# rapidshark-half-h-bridge-mk-1_0.net
KiCad netlist of a schematic drawn in EAGLE
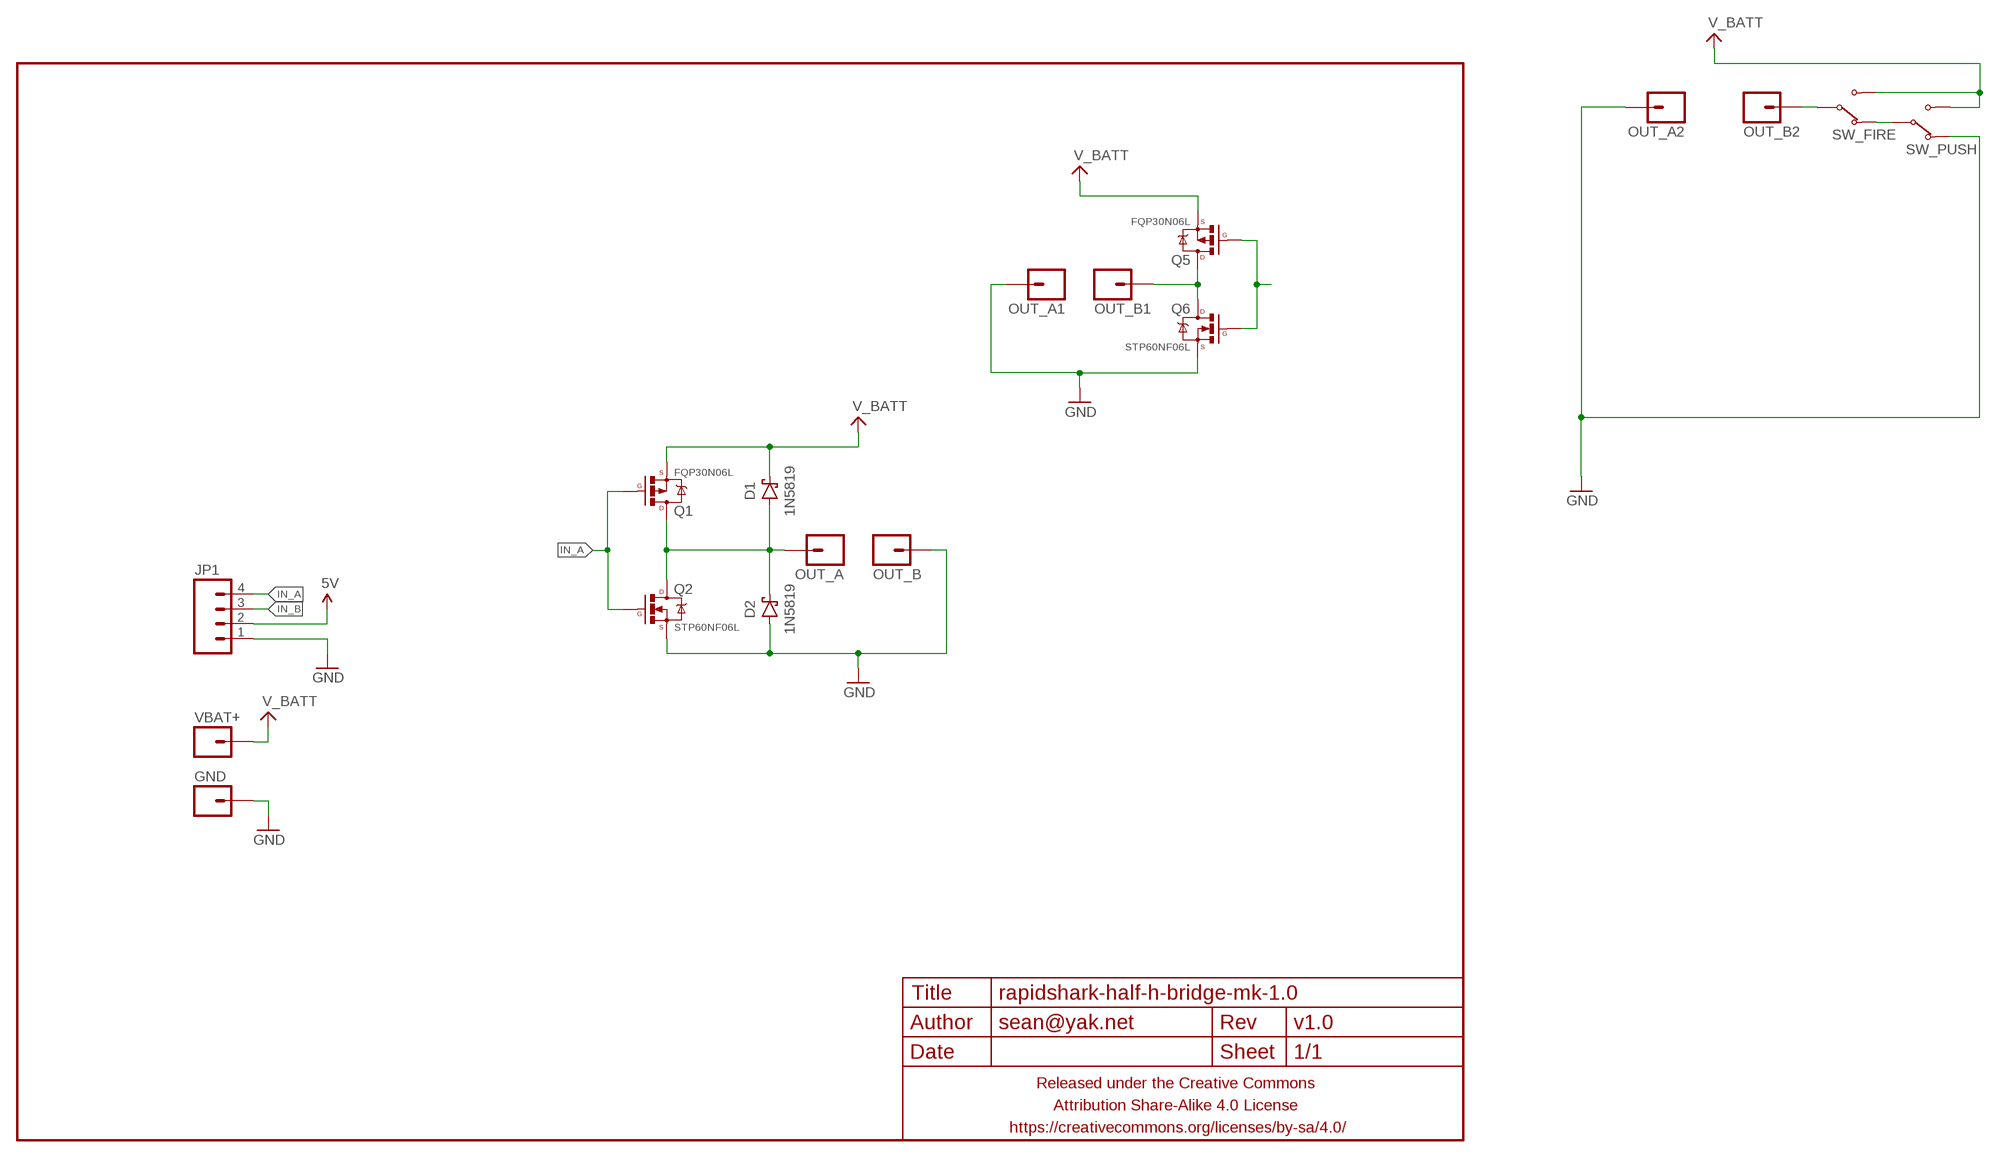
[diagram p0: schematic, sheet 1]

(export (version "E")
  (design (tool "Eeschema 10.0.6"))
  (components
    (comp (ref "D1")
      (value "1N5819")
      (footprint "eagle-import:DIODE-SCHOTTKY-10.16MM")
      (libsource (lib "eagle-import") (part "DIODE-SCHOTTKYPTH-10.16MM"))
    )
    (comp (ref "D2")
      (value "1N5819")
      (footprint "eagle-import:DIODE-SCHOTTKY-10.16MM")
      (libsource (lib "eagle-import") (part "DIODE-SCHOTTKYPTH-10.16MM"))
    )
    (comp (ref "FRAME1")
      (value "FRAME-LETTERNO_PACKAGE")
      (footprint "eagle-import:DUMMY")
      (fields (field (name "DESIGNER") "sean@yak.net") (field (name "VERSION") "v1.0"))
      (libsource (lib "eagle-import") (part "FRAME-LETTERNO_PACKAGE"))
    )
    (comp (ref "GND")
      (value "M0112AWG")
      (footprint "eagle-import:1X01-12AWG")
      (libsource (lib "eagle-import") (part "M0112AWG"))
    )
    (comp (ref "JP1")
      (value "M04PTH")
      (footprint "eagle-import:1X04-PTH-VERT")
      (libsource (lib "eagle-import") (part "M04PTH"))
    )
    (comp (ref "OUT_A")
      (value "M0112AWG")
      (footprint "eagle-import:1X01-12AWG")
      (libsource (lib "eagle-import") (part "M0112AWG"))
    )
    (comp (ref "OUT_A1")
      (value "M0112AWG")
      (footprint "eagle-import:1X01-12AWG")
      (libsource (lib "eagle-import") (part "M0112AWG"))
    )
    (comp (ref "OUT_A2")
      (value "M0112AWG")
      (footprint "eagle-import:1X01-12AWG")
      (libsource (lib "eagle-import") (part "M0112AWG"))
    )
    (comp (ref "OUT_B")
      (value "M0112AWG")
      (footprint "eagle-import:1X01-12AWG")
      (libsource (lib "eagle-import") (part "M0112AWG"))
    )
    (comp (ref "OUT_B1")
      (value "M0112AWG")
      (footprint "eagle-import:1X01-12AWG")
      (libsource (lib "eagle-import") (part "M0112AWG"))
    )
    (comp (ref "OUT_B2")
      (value "M0112AWG")
      (footprint "eagle-import:1X01-12AWG")
      (libsource (lib "eagle-import") (part "M0112AWG"))
    )
    (comp (ref "Q1")
      (value "FQP30N06L")
      (footprint "eagle-import:TO220-THERMPAD")
      (libsource (lib "eagle-import") (part "MOSFET-PCHANNELTO-220-THERMPAD"))
    )
    (comp (ref "Q2")
      (value "STP60NF06L")
      (footprint "eagle-import:TO220-THERMPAD")
      (libsource (lib "eagle-import") (part "MOSFET-NCHANNELTO-220"))
    )
    (comp (ref "Q5")
      (value "FQP30N06L")
      (footprint "eagle-import:TO220-THERMPAD")
      (libsource (lib "eagle-import") (part "MOSFET-PCHANNELTO-220-THERMPAD"))
    )
    (comp (ref "Q6")
      (value "STP60NF06L")
      (footprint "eagle-import:TO220-THERMPAD")
      (libsource (lib "eagle-import") (part "MOSFET-NCHANNELTO-220"))
    )
    (comp (ref "SW_FIRE")
      (value "SWITCH-SPDTPTH-VERT-2.54MM")
      (footprint "eagle-import:SWITCH-SPDT")
      (libsource (lib "eagle-import") (part "SWITCH-SPDTPTH-VERT-2.54MM"))
    )
    (comp (ref "SW_PUSH")
      (value "SWITCH-SPDTPTH-VERT-2.54MM")
      (footprint "eagle-import:SWITCH-SPDT")
      (libsource (lib "eagle-import") (part "SWITCH-SPDTPTH-VERT-2.54MM"))
    )
    (comp (ref "VBAT+")
      (value "M0112AWG")
      (footprint "eagle-import:1X01-12AWG")
      (libsource (lib "eagle-import") (part "M0112AWG"))
    )
  )
  (nets
    (net (code "1") (name "5V") (class "Default")
      (node (ref "JP1") (pin "2") (pinfunction "2_2") (pintype "passive"))
    )
    (net (code "2") (name "GND") (class "Default")
      (node (ref "D2") (pin "A") (pinfunction "A_A") (pintype "passive"))
      (node (ref "GND") (pin "1") (pinfunction "1_1") (pintype "passive"))
      (node (ref "JP1") (pin "1") (pinfunction "1_1") (pintype "passive"))
      (node (ref "OUT_A1") (pin "1") (pinfunction "1_1") (pintype "passive"))
      (node (ref "OUT_A2") (pin "1") (pinfunction "1_1") (pintype "passive"))
      (node (ref "OUT_B") (pin "1") (pinfunction "1_1") (pintype "passive"))
      (node (ref "Q2") (pin "3") (pinfunction "S_3") (pintype "passive"))
      (node (ref "Q6") (pin "3") (pinfunction "S_3") (pintype "passive"))
      (node (ref "SW_PUSH") (pin "1") (pinfunction "NC_1") (pintype "passive"))
    )
    (net (code "3") (name "IN_A") (class "Default")
      (node (ref "JP1") (pin "4") (pinfunction "4_4") (pintype "passive"))
      (node (ref "Q1") (pin "1") (pinfunction "G_1") (pintype "passive"))
      (node (ref "Q2") (pin "1") (pinfunction "G_1") (pintype "passive"))
    )
    (net (code "4") (name "IN_B") (class "Default")
      (node (ref "JP1") (pin "3") (pinfunction "3_3") (pintype "passive"))
    )
    (net (code "5") (name "Net-(D1-PadA)") (class "Default")
      (node (ref "D1") (pin "A") (pinfunction "A_A") (pintype "passive"))
      (node (ref "D2") (pin "C") (pinfunction "C_C") (pintype "passive"))
      (node (ref "OUT_A") (pin "1") (pinfunction "1_1") (pintype "passive"))
      (node (ref "Q1") (pin "2@1") (pinfunction "D_2@1") (pintype "passive"))
      (node (ref "Q1") (pin "2@2") (pinfunction "D_2@2") (pintype "passive"))
      (node (ref "Q2") (pin "2@1") (pinfunction "D_2@1") (pintype "passive"))
      (node (ref "Q2") (pin "2@2") (pinfunction "D_2@2") (pintype "passive"))
    )
    (net (code "6") (name "Net-(OUT_B1-Pad1)") (class "Default")
      (node (ref "OUT_B1") (pin "1") (pinfunction "1_1") (pintype "passive"))
      (node (ref "Q5") (pin "2@1") (pinfunction "D_2@1") (pintype "passive"))
      (node (ref "Q5") (pin "2@2") (pinfunction "D_2@2") (pintype "passive"))
      (node (ref "Q6") (pin "2@1") (pinfunction "D_2@1") (pintype "passive"))
      (node (ref "Q6") (pin "2@2") (pinfunction "D_2@2") (pintype "passive"))
    )
    (net (code "7") (name "Net-(Q5-G)") (class "Default")
      (node (ref "Q5") (pin "1") (pinfunction "G_1") (pintype "passive"))
      (node (ref "Q6") (pin "1") (pinfunction "G_1") (pintype "passive"))
    )
    (net (code "8") (name "Net-(SW_FIRE-COM)") (class "Default")
      (node (ref "OUT_B2") (pin "1") (pinfunction "1_1") (pintype "passive"))
      (node (ref "SW_FIRE") (pin "2") (pinfunction "COM_2") (pintype "passive"))
    )
    (net (code "9") (name "Net-(SW_FIRE-NC)") (class "Default")
      (node (ref "SW_FIRE") (pin "1") (pinfunction "NC_1") (pintype "passive"))
      (node (ref "SW_PUSH") (pin "2") (pinfunction "COM_2") (pintype "passive"))
    )
    (net (code "10") (name "V_BATT") (class "Default")
      (node (ref "D1") (pin "C") (pinfunction "C_C") (pintype "passive"))
      (node (ref "Q1") (pin "3") (pinfunction "S_3") (pintype "passive"))
      (node (ref "Q5") (pin "3") (pinfunction "S_3") (pintype "passive"))
      (node (ref "SW_FIRE") (pin "3") (pinfunction "NO_3") (pintype "passive"))
      (node (ref "SW_PUSH") (pin "3") (pinfunction "NO_3") (pintype "passive"))
      (node (ref "VBAT+") (pin "1") (pinfunction "1_1") (pintype "passive"))
    )
  )
)
